# Franzininho_CNC.net
KiCad netlist of a schematic drawn in EAGLE
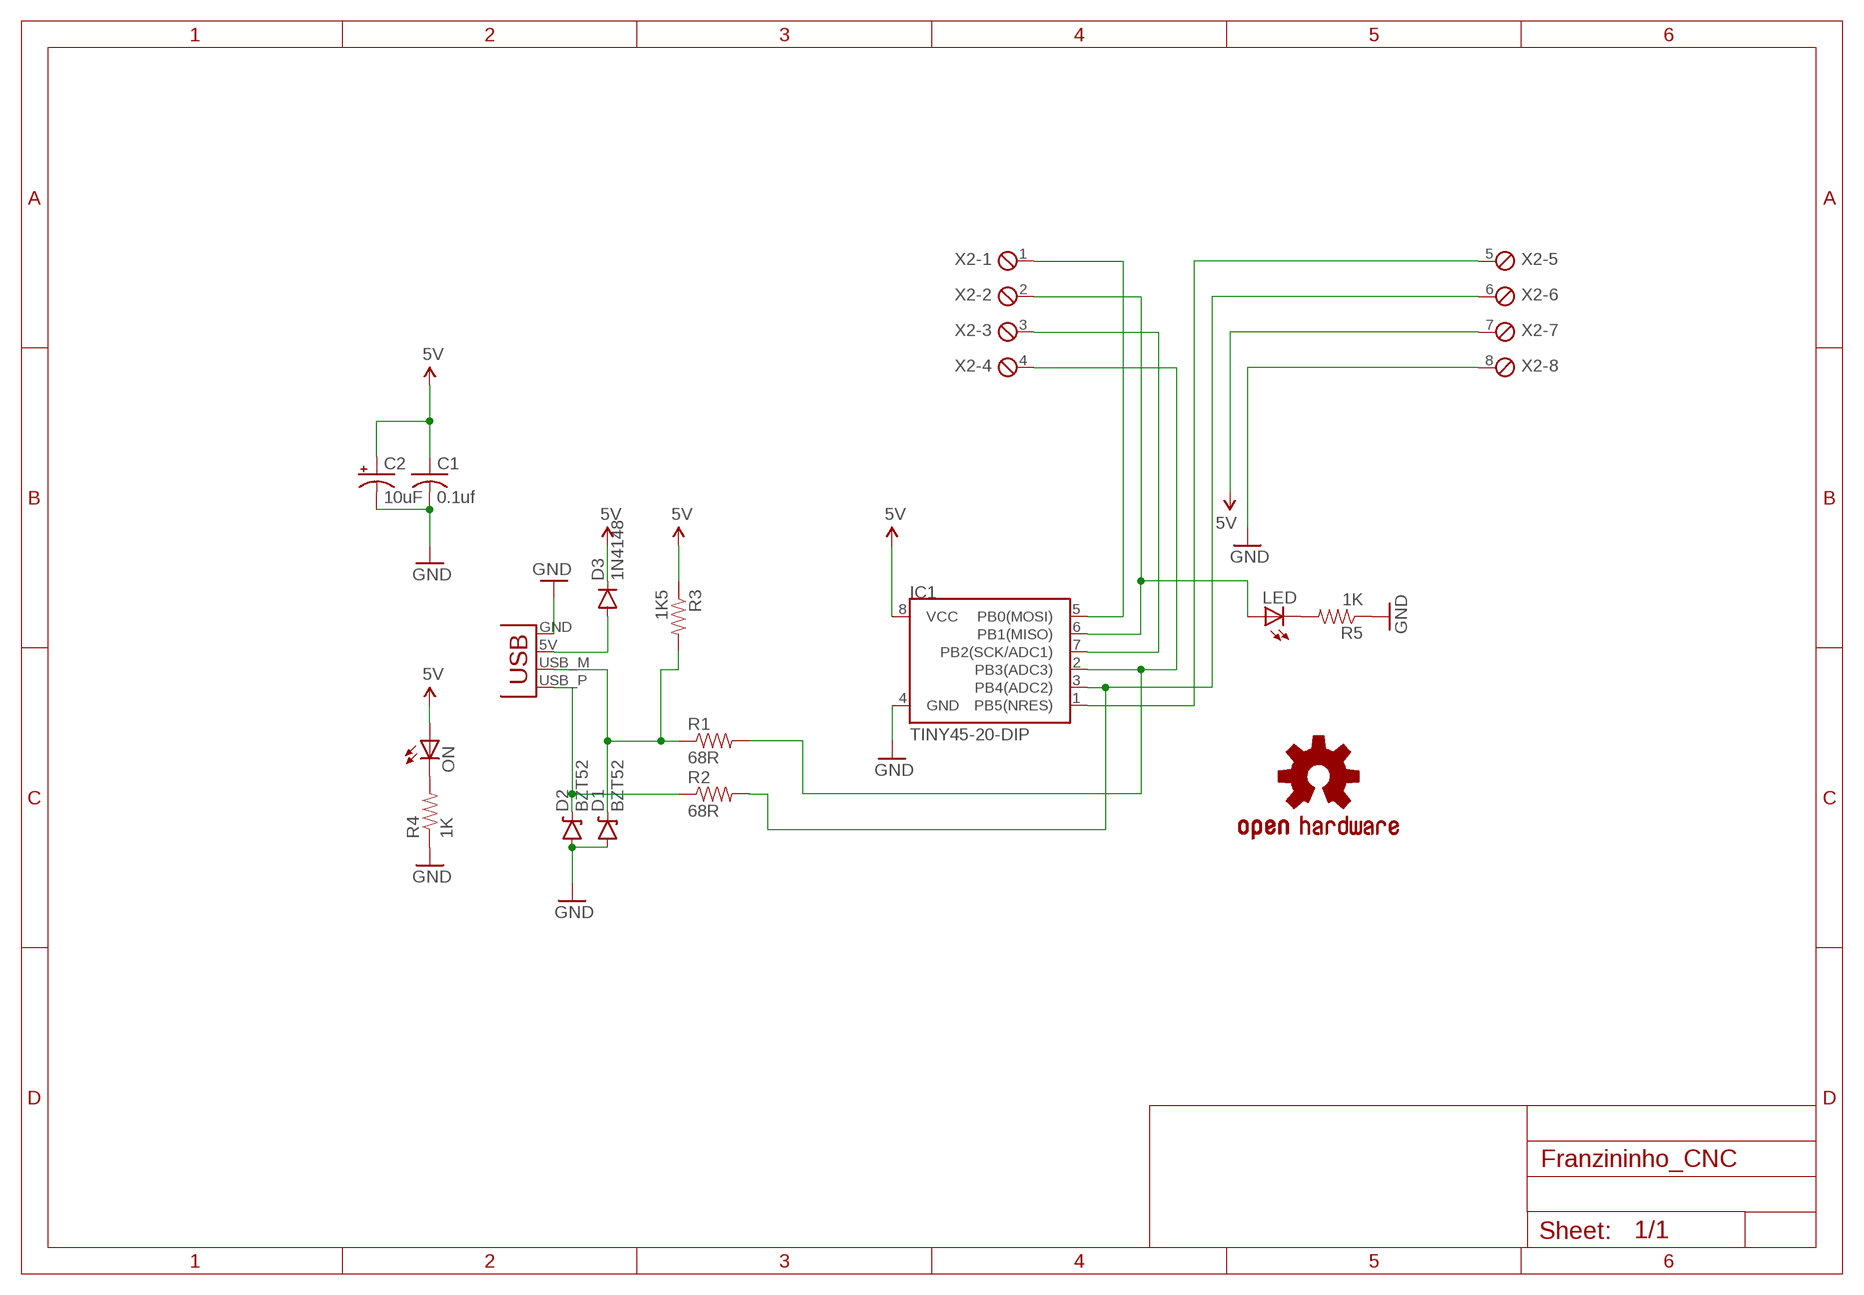
[diagram p0: schematic, sheet 1]

(export (version "E")
  (design (tool "Eeschema 10.0.6"))
  (components
    (comp (ref "C1")
      (value "0.1uf")
      (footprint "eagle-import:C025-025X050")
      (libsource (lib "eagle-import") (part "C-US025-025X050"))
    )
    (comp (ref "C2")
      (value "10uF")
      (footprint "eagle-import:E2,5-6E")
      (libsource (lib "eagle-import") (part "CPOL-USE2,5-6E"))
    )
    (comp (ref "D1")
      (value "BZT52")
      (footprint "eagle-import:DIODE-BZT52")
      (libsource (lib "eagle-import") (part "DIODE-ZENER"))
    )
    (comp (ref "D2")
      (value "BZT52")
      (footprint "eagle-import:DIODE-BZT52")
      (libsource (lib "eagle-import") (part "DIODE-ZENER"))
    )
    (comp (ref "D3")
      (value "1N4148")
      (footprint "eagle-import:DIODE-1N4148")
      (libsource (lib "eagle-import") (part "DIODE1N4148"))
    )
    (comp (ref "IC1")
      (value "TINY45-20-DIP")
      (footprint "eagle-import:DIP08")
      (libsource (lib "eagle-import") (part "ATTINY45TINY45-20-DIP"))
    )
    (comp (ref "LED")
      (value "LED3MM")
      (footprint "eagle-import:LED3MM")
      (libsource (lib "eagle-import") (part "LED3MM"))
    )
    (comp (ref "LOGO1")
      (value "OSHW-LOGOL")
      (footprint "eagle-import:OSHW-LOGO-L")
      (libsource (lib "eagle-import") (part "OSHW-LOGOL"))
    )
    (comp (ref "ON")
      (value "LED3MM")
      (footprint "eagle-import:LED3MM")
      (libsource (lib "eagle-import") (part "LED3MM"))
    )
    (comp (ref "R1")
      (value "68R")
      (footprint "eagle-import:AXIAL-0.4")
      (libsource (lib "eagle-import") (part "RESISTORPTH-1/4W"))
    )
    (comp (ref "R2")
      (value "68R")
      (footprint "eagle-import:AXIAL-0.4")
      (libsource (lib "eagle-import") (part "RESISTORPTH-1/4W"))
    )
    (comp (ref "R3")
      (value "1K5")
      (footprint "eagle-import:AXIAL-0.4")
      (libsource (lib "eagle-import") (part "RESISTORPTH-1/4W"))
    )
    (comp (ref "R4")
      (value "1K")
      (footprint "eagle-import:AXIAL-0.4")
      (libsource (lib "eagle-import") (part "RESISTORPTH-1/4W"))
    )
    (comp (ref "R5")
      (value "1K")
      (footprint "eagle-import:AXIAL-0.4")
      (libsource (lib "eagle-import") (part "RESISTORPTH-1/4W"))
    )
    (comp (ref "X1")
      (value "USBPCB")
      (footprint "eagle-import:USB-A-PCB")
      (libsource (lib "eagle-import") (part "USBPCB"))
    )
    (comp (ref "X2")
      (value "MPT8")
      (footprint "eagle-import:8POL254")
      (libsource (lib "eagle-import") (part "MPT8"))
    )
  )
  (nets
    (net (code "1") (name "5V") (class "Default")
      (node (ref "C1") (pin "1") (pinfunction "1_1") (pintype "passive"))
      (node (ref "C2") (pin "+") (pinfunction "+_+") (pintype "passive"))
      (node (ref "D3") (pin "C") (pinfunction "C_C") (pintype "passive"))
      (node (ref "IC1") (pin "8") (pinfunction "VCC_8") (pintype "bidirectional"))
      (node (ref "ON") (pin "A") (pinfunction "A_A") (pintype "passive"))
      (node (ref "R3") (pin "P$1") (pinfunction "1_P$1") (pintype "passive"))
      (node (ref "X2") (pin "7") (pinfunction "1_7") (pintype "passive"))
    )
    (net (code "2") (name "GND") (class "Default")
      (node (ref "C1") (pin "2") (pinfunction "2_2") (pintype "passive"))
      (node (ref "C2") (pin "-") (pinfunction "-_-") (pintype "passive"))
      (node (ref "D1") (pin "A") (pinfunction "A_A") (pintype "passive"))
      (node (ref "D2") (pin "A") (pinfunction "A_A") (pintype "passive"))
      (node (ref "IC1") (pin "4") (pinfunction "GND_4") (pintype "bidirectional"))
      (node (ref "R4") (pin "P$1") (pinfunction "1_P$1") (pintype "passive"))
      (node (ref "R5") (pin "P$1") (pinfunction "1_P$1") (pintype "passive"))
      (node (ref "X1") (pin "GND") (pinfunction "GND_GND") (pintype "bidirectional"))
      (node (ref "X2") (pin "8") (pinfunction "1_8") (pintype "passive"))
    )
    (net (code "3") (name "Net-(IC1-PB0(MOSI))") (class "Default")
      (node (ref "IC1") (pin "5") (pinfunction "PB0(MOSI)_5") (pintype "bidirectional"))
      (node (ref "X2") (pin "1") (pinfunction "1_1") (pintype "passive"))
    )
    (net (code "4") (name "Net-(IC1-PB1(MISO))") (class "Default")
      (node (ref "IC1") (pin "6") (pinfunction "PB1(MISO)_6") (pintype "bidirectional"))
      (node (ref "LED") (pin "A") (pinfunction "A_A") (pintype "passive"))
      (node (ref "X2") (pin "2") (pinfunction "1_2") (pintype "passive"))
    )
    (net (code "5") (name "Net-(IC1-PB2(SCK{slash}ADC1))") (class "Default")
      (node (ref "IC1") (pin "7") (pinfunction "PB2(SCK/ADC1)_7") (pintype "bidirectional"))
      (node (ref "X2") (pin "3") (pinfunction "1_3") (pintype "passive"))
    )
    (net (code "6") (name "Net-(IC1-PB3(ADC3))") (class "Default")
      (node (ref "IC1") (pin "2") (pinfunction "PB3(ADC3)_2") (pintype "bidirectional"))
      (node (ref "R1") (pin "P$2") (pinfunction "2_P$2") (pintype "passive"))
      (node (ref "X2") (pin "4") (pinfunction "1_4") (pintype "passive"))
    )
    (net (code "7") (name "Net-(IC1-PB4(ADC2))") (class "Default")
      (node (ref "IC1") (pin "3") (pinfunction "PB4(ADC2)_3") (pintype "bidirectional"))
      (node (ref "R2") (pin "P$2") (pinfunction "2_P$2") (pintype "passive"))
      (node (ref "X2") (pin "6") (pinfunction "1_6") (pintype "passive"))
    )
    (net (code "8") (name "Net-(IC1-PB5(NRES))") (class "Default")
      (node (ref "IC1") (pin "1") (pinfunction "PB5(NRES)_1") (pintype "bidirectional"))
      (node (ref "X2") (pin "5") (pinfunction "1_5") (pintype "passive"))
    )
    (net (code "9") (name "Net-(LED-C)") (class "Default")
      (node (ref "LED") (pin "K") (pinfunction "C_K") (pintype "passive"))
      (node (ref "R5") (pin "P$2") (pinfunction "2_P$2") (pintype "passive"))
    )
    (net (code "10") (name "Net-(ON-C)") (class "Default")
      (node (ref "ON") (pin "K") (pinfunction "C_K") (pintype "passive"))
      (node (ref "R4") (pin "P$2") (pinfunction "2_P$2") (pintype "passive"))
    )
    (net (code "11") (name "Net-(R1-1)") (class "Default")
      (node (ref "D1") (pin "C") (pinfunction "C_C") (pintype "passive"))
      (node (ref "R1") (pin "P$1") (pinfunction "1_P$1") (pintype "passive"))
      (node (ref "R3") (pin "P$2") (pinfunction "2_P$2") (pintype "passive"))
      (node (ref "X1") (pin "USB_M") (pinfunction "D-_USB_M") (pintype "bidirectional"))
    )
    (net (code "12") (name "Net-(R2-1)") (class "Default")
      (node (ref "D2") (pin "C") (pinfunction "C_C") (pintype "passive"))
      (node (ref "R2") (pin "P$1") (pinfunction "1_P$1") (pintype "passive"))
      (node (ref "X1") (pin "USB_P") (pinfunction "D+_USB_P") (pintype "bidirectional"))
    )
    (net (code "13") (name "Net-(X1-VBUS)") (class "Default")
      (node (ref "D3") (pin "A") (pinfunction "A_A") (pintype "passive"))
      (node (ref "X1") (pin "5V") (pinfunction "VBUS_5V") (pintype "bidirectional"))
    )
  )
)
